# ws2812_2020_breakout_mini.net
KiCad netlist of a schematic drawn in Altium Designer
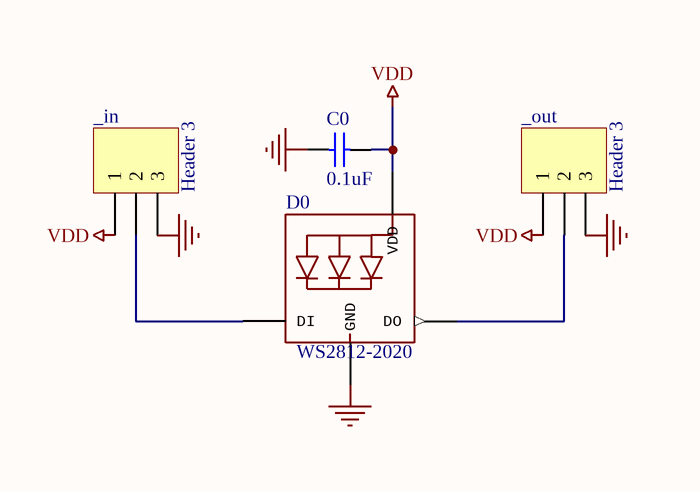
[diagram p0: ws2812_2020_breakout_mini.SchDoc]

(export (version "E")
  (design (tool "Eeschema 10.0.6"))
  (components
    (comp (ref "C0")
      (value "0.1uF")
      (footprint "CAP_0402R")
      (description "Capacitor")
      (libsource (lib "ws2812_2020_breakout") (part "CAP"))
    )
    (comp (ref "D0")
      (value "WS2812-2020")
      (footprint "WS2812-2020")
      (description "Intelligent control LED integrated light source, low current, 2020 package")
      (fields (field (name "MANUFACTURER") "Worldsemi"))
      (libsource (lib "ws2812_2020_breakout") (part "WS2812-2020"))
    )
    (comp (ref "_in")
      (value "Header 3")
      (footprint "HDR1X3_SWD")
      (description "Header, 3-Pin")
      (libsource (lib "ws2812_2020_breakout") (part "Header 3"))
    )
    (comp (ref "_out")
      (value "Header 3")
      (footprint "HDR1X3_SWD")
      (description "Header, 3-Pin")
      (libsource (lib "ws2812_2020_breakout") (part "Header 3"))
    )
  )
  (nets
    (net (code "1") (name "GND") (class "Default")
      (node (ref "C0") (pin "1") (pinfunction "1_1") (pintype "passive"))
      (node (ref "D0") (pin "2") (pinfunction "GND_2") (pintype "power_in"))
      (node (ref "_in") (pin "3") (pinfunction "3_3") (pintype "passive"))
      (node (ref "_out") (pin "3") (pinfunction "3_3") (pintype "passive"))
    )
    (net (code "2") (name "Net-(D0-DI)") (class "Default")
      (node (ref "D0") (pin "3") (pinfunction "DI_3") (pintype "passive"))
      (node (ref "_in") (pin "2") (pinfunction "2_2") (pintype "passive"))
    )
    (net (code "3") (name "Net-(D0-DO)") (class "Default")
      (node (ref "D0") (pin "1") (pinfunction "DO_1") (pintype "output"))
      (node (ref "_out") (pin "2") (pinfunction "2_2") (pintype "passive"))
    )
    (net (code "4") (name "VDD") (class "Default")
      (node (ref "C0") (pin "2") (pinfunction "2_2") (pintype "passive"))
      (node (ref "D0") (pin "4") (pinfunction "VDD_4") (pintype "power_in"))
      (node (ref "_in") (pin "1") (pinfunction "1_1") (pintype "passive"))
      (node (ref "_out") (pin "1") (pinfunction "1_1") (pintype "passive"))
    )
  )
)
